# 8.net
KiCad netlist of a schematic drawn in Altium Designer
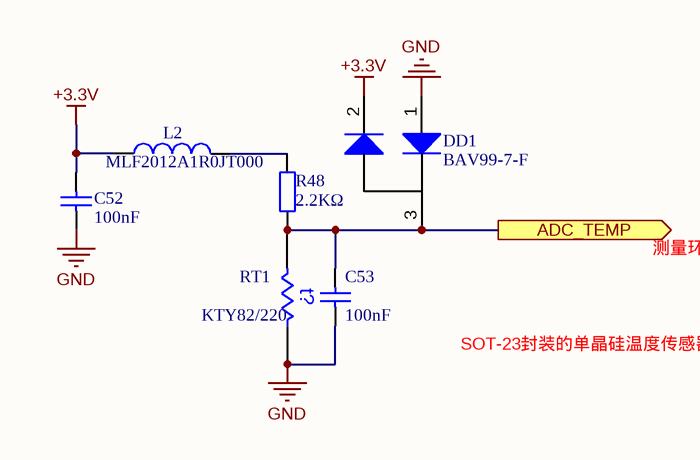
[diagram p0: 8_电子天平_温度检测.SchDoc]

(export (version "E")
  (design (tool "Eeschema 10.0.6"))
  (components
    (comp (ref "C52")
      (value "100nF")
      (footprint "LC-0805_C")
      (description "MLCC")
      (fields (field (name "PUBLISHER") "Altium Limited"))
      (libsource (lib "Miscellaneous Devices") (part "Cap"))
    )
    (comp (ref "C53")
      (value "100nF")
      (footprint "LC-0805_C")
      (description "MLCC")
      (fields (field (name "PUBLISHER") "Altium Limited"))
      (libsource (lib "Miscellaneous Devices") (part "Cap"))
    )
    (comp (ref "DD1")
      (value "BAV99-7-F")
      (footprint "LC-SOT-23(SOT-23-3)")
      (description "开关二极管")
      (libsource (lib "Miscellaneous Devices LC") (part "SOT-23 BAV99 A7W"))
    )
    (comp (ref "L2")
      (value "MLF2012A1R0JT000")
      (footprint "LC-0805_L")
      (description "贴片电感")
      (fields (field (name "PUBLISHER") "Altium Limited"))
      (libsource (lib "Miscellaneous Devices") (part "Inductor"))
    )
    (comp (ref "R48")
      (value "2.2KΩ")
      (footprint "LC-0805_R")
      (description "贴片电阻")
      (libsource (lib "Miscellaneous Devices LC") (part "0805 470KΩ (4703) 1%"))
    )
    (comp (ref "RT1")
      (value "KTY82/220")
      (footprint "LC-SOT-23(SOT-23-3)")
      (description "Thermistor")
      (fields (field (name "PUBLISHER") "Altium Limited"))
      (libsource (lib "Miscellaneous Devices") (part "Res Thermal"))
    )
  )
  (nets
    (net (code "1") (name "+3.3V") (class "Default")
      (node (ref "C52") (pin "2") (pinfunction "2_2") (pintype "passive"))
      (node (ref "DD1") (pin "2") (pinfunction "A_2") (pintype "passive"))
      (node (ref "L2") (pin "2") (pinfunction "2_2") (pintype "passive"))
    )
    (net (code "2") (name "/ADC_TEMP") (class "Default")
      (node (ref "C53") (pin "2") (pinfunction "2_2") (pintype "passive"))
      (node (ref "DD1") (pin "3") (pinfunction "K_3") (pintype "passive"))
      (node (ref "R48") (pin "1") (pinfunction "1_1") (pintype "passive"))
      (node (ref "RT1") (pin "2") (pinfunction "2_2") (pintype "passive"))
    )
    (net (code "3") (name "GND") (class "Default")
      (node (ref "C52") (pin "1") (pinfunction "1_1") (pintype "passive"))
      (node (ref "C53") (pin "1") (pinfunction "1_1") (pintype "passive"))
      (node (ref "DD1") (pin "1") (pinfunction "A_1") (pintype "passive"))
      (node (ref "RT1") (pin "1") (pinfunction "1_1") (pintype "passive"))
    )
    (net (code "4") (name "Net-(L2-Pad1)") (class "Default")
      (node (ref "L2") (pin "1") (pinfunction "1_1") (pintype "passive"))
      (node (ref "R48") (pin "2") (pinfunction "2_2") (pintype "passive"))
    )
  )
)
